# Reference.net
KiCad netlist of a schematic drawn in EAGLE
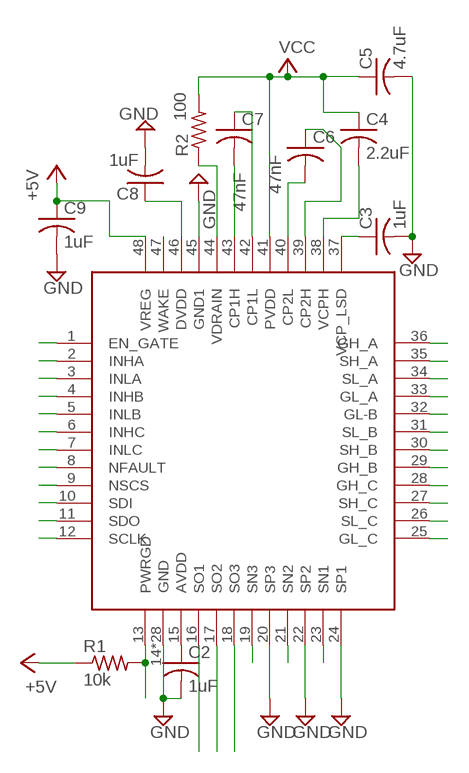
[diagram p0: schematic, sheet 1]

(export (version "E")
  (design (tool "Eeschema 10.0.6"))
  (components
    (comp (ref "C2")
      (value "1uF")
      (footprint "eagle-import:C0805")
      (libsource (lib "eagle-import") (part "C-USC0805"))
    )
    (comp (ref "C3")
      (value "1uF")
      (footprint "eagle-import:C0805")
      (libsource (lib "eagle-import") (part "C-USC0805"))
    )
    (comp (ref "C4")
      (value "2.2uF")
      (footprint "eagle-import:C0805")
      (libsource (lib "eagle-import") (part "C-USC0805"))
    )
    (comp (ref "C5")
      (value "4.7uF")
      (footprint "eagle-import:C0805")
      (libsource (lib "eagle-import") (part "C-USC0805"))
    )
    (comp (ref "C6")
      (value "47nF")
      (footprint "eagle-import:C0805")
      (libsource (lib "eagle-import") (part "C-USC0805"))
    )
    (comp (ref "C7")
      (value "47nF")
      (footprint "eagle-import:C0805")
      (libsource (lib "eagle-import") (part "C-USC0805"))
    )
    (comp (ref "C8")
      (value "1uF")
      (footprint "eagle-import:C0805")
      (libsource (lib "eagle-import") (part "C-USC0805"))
    )
    (comp (ref "C9")
      (value "1uF")
      (footprint "eagle-import:C0805")
      (libsource (lib "eagle-import") (part "C-USC0805"))
    )
    (comp (ref "R1")
      (value "10k")
      (footprint "eagle-import:M0805")
      (libsource (lib "eagle-import") (part "R-US_M0805"))
    )
    (comp (ref "R2")
      (value "100")
      (footprint "eagle-import:M0805")
      (libsource (lib "eagle-import") (part "R-US_M0805"))
    )
    (comp (ref "U$1")
      (value "DRV8305")
      (footprint "eagle-import:PFB_S-PQFP-G48")
      (libsource (lib "eagle-import") (part "DRV8305"))
    )
  )
  (nets
    (net (code "1") (name "+5V") (class "Default")
      (node (ref "C9") (pin "1") (pinfunction "1_1") (pintype "passive"))
      (node (ref "R1") (pin "1") (pinfunction "1_1") (pintype "passive"))
      (node (ref "U$1") (pin "48") (pinfunction "VREG_48") (pintype "bidirectional"))
    )
    (net (code "2") (name "/SL_A") (class "Default")
      (node (ref "U$1") (pin "23") (pinfunction "SN1_23") (pintype "bidirectional"))
      (node (ref "U$1") (pin "34") (pinfunction "SL_A_34") (pintype "bidirectional"))
    )
    (net (code "3") (name "/SL_B") (class "Default")
      (node (ref "U$1") (pin "21") (pinfunction "SN2_21") (pintype "bidirectional"))
      (node (ref "U$1") (pin "31") (pinfunction "SL_B_31") (pintype "bidirectional"))
    )
    (net (code "4") (name "/SL_C") (class "Default")
      (node (ref "U$1") (pin "19") (pinfunction "SN3_19") (pintype "bidirectional"))
      (node (ref "U$1") (pin "26") (pinfunction "SL_C_26") (pintype "bidirectional"))
    )
    (net (code "5") (name "GND") (class "Default")
      (node (ref "C2") (pin "2") (pinfunction "2_2") (pintype "passive"))
      (node (ref "C3") (pin "2") (pinfunction "2_2") (pintype "passive"))
      (node (ref "C5") (pin "2") (pinfunction "2_2") (pintype "passive"))
      (node (ref "C8") (pin "2") (pinfunction "2_2") (pintype "passive"))
      (node (ref "C9") (pin "2") (pinfunction "2_2") (pintype "passive"))
      (node (ref "U$1") (pin "14") (pinfunction "GND_14") (pintype "bidirectional"))
      (node (ref "U$1") (pin "20") (pinfunction "SP3_20") (pintype "bidirectional"))
      (node (ref "U$1") (pin "22") (pinfunction "SP2_22") (pintype "bidirectional"))
      (node (ref "U$1") (pin "24") (pinfunction "SP1_24") (pintype "bidirectional"))
      (node (ref "U$1") (pin "45") (pinfunction "GND1_45") (pintype "bidirectional"))
      (node (ref "U$1") (pin "P$1") (pinfunction "GND_P$1") (pintype "bidirectional"))
      (node (ref "U$1") (pin "P$10") (pinfunction "GND_P$10") (pintype "bidirectional"))
      (node (ref "U$1") (pin "P$11") (pinfunction "GND_P$11") (pintype "bidirectional"))
      (node (ref "U$1") (pin "P$12") (pinfunction "GND_P$12") (pintype "bidirectional"))
      (node (ref "U$1") (pin "P$13") (pinfunction "GND_P$13") (pintype "bidirectional"))
      (node (ref "U$1") (pin "P$14") (pinfunction "GND_P$14") (pintype "bidirectional"))
      (node (ref "U$1") (pin "P$15") (pinfunction "GND_P$15") (pintype "bidirectional"))
      (node (ref "U$1") (pin "P$16") (pinfunction "GND_P$16") (pintype "bidirectional"))
      (node (ref "U$1") (pin "P$17") (pinfunction "GND_P$17") (pintype "bidirectional"))
      (node (ref "U$1") (pin "P$18") (pinfunction "GND_P$18") (pintype "bidirectional"))
      (node (ref "U$1") (pin "P$19") (pinfunction "GND_P$19") (pintype "bidirectional"))
      (node (ref "U$1") (pin "P$2") (pinfunction "GND_P$2") (pintype "bidirectional"))
      (node (ref "U$1") (pin "P$20") (pinfunction "GND_P$20") (pintype "bidirectional"))
      (node (ref "U$1") (pin "P$21") (pinfunction "GND_P$21") (pintype "bidirectional"))
      (node (ref "U$1") (pin "P$22") (pinfunction "GND_P$22") (pintype "bidirectional"))
      (node (ref "U$1") (pin "P$23") (pinfunction "GND_P$23") (pintype "bidirectional"))
      (node (ref "U$1") (pin "P$24") (pinfunction "GND_P$24") (pintype "bidirectional"))
      (node (ref "U$1") (pin "P$25") (pinfunction "GND_P$25") (pintype "bidirectional"))
      (node (ref "U$1") (pin "P$26") (pinfunction "GND_P$26") (pintype "bidirectional"))
      (node (ref "U$1") (pin "P$27") (pinfunction "GND_P$27") (pintype "bidirectional"))
      (node (ref "U$1") (pin "P$3") (pinfunction "GND_P$3") (pintype "bidirectional"))
      (node (ref "U$1") (pin "P$4") (pinfunction "GND_P$4") (pintype "bidirectional"))
      (node (ref "U$1") (pin "P$5") (pinfunction "GND_P$5") (pintype "bidirectional"))
      (node (ref "U$1") (pin "P$6") (pinfunction "GND_P$6") (pintype "bidirectional"))
      (node (ref "U$1") (pin "P$7") (pinfunction "GND_P$7") (pintype "bidirectional"))
      (node (ref "U$1") (pin "P$8") (pinfunction "GND_P$8") (pintype "bidirectional"))
      (node (ref "U$1") (pin "P$9") (pinfunction "GND_P$9") (pintype "bidirectional"))
    )
    (net (code "6") (name "Net-(U$1-AVDD)") (class "Default")
      (node (ref "C2") (pin "1") (pinfunction "1_1") (pintype "passive"))
      (node (ref "U$1") (pin "15") (pinfunction "AVDD_15") (pintype "bidirectional"))
    )
    (net (code "7") (name "Net-(U$1-CP1H)") (class "Default")
      (node (ref "C7") (pin "2") (pinfunction "2_2") (pintype "passive"))
      (node (ref "U$1") (pin "43") (pinfunction "CP1H_43") (pintype "bidirectional"))
    )
    (net (code "8") (name "Net-(U$1-CP1L)") (class "Default")
      (node (ref "C7") (pin "1") (pinfunction "1_1") (pintype "passive"))
      (node (ref "U$1") (pin "42") (pinfunction "CP1L_42") (pintype "bidirectional"))
    )
    (net (code "9") (name "Net-(U$1-CP2H)") (class "Default")
      (node (ref "C6") (pin "1") (pinfunction "1_1") (pintype "passive"))
      (node (ref "U$1") (pin "39") (pinfunction "CP2H_39") (pintype "bidirectional"))
    )
    (net (code "10") (name "Net-(U$1-CP2L)") (class "Default")
      (node (ref "C6") (pin "2") (pinfunction "2_2") (pintype "passive"))
      (node (ref "U$1") (pin "40") (pinfunction "CP2L_40") (pintype "bidirectional"))
    )
    (net (code "11") (name "Net-(U$1-DVDD)") (class "Default")
      (node (ref "C8") (pin "1") (pinfunction "1_1") (pintype "passive"))
      (node (ref "U$1") (pin "46") (pinfunction "DVDD_46") (pintype "bidirectional"))
    )
    (net (code "12") (name "Net-(U$1-PWRGD)") (class "Default")
      (node (ref "R1") (pin "2") (pinfunction "2_2") (pintype "passive"))
      (node (ref "U$1") (pin "13") (pinfunction "PWRGD_13") (pintype "bidirectional"))
    )
    (net (code "13") (name "Net-(U$1-VCPH)") (class "Default")
      (node (ref "C4") (pin "2") (pinfunction "2_2") (pintype "passive"))
      (node (ref "U$1") (pin "38") (pinfunction "VCPH_38") (pintype "bidirectional"))
    )
    (net (code "14") (name "Net-(U$1-VCP_LSD)") (class "Default")
      (node (ref "C3") (pin "1") (pinfunction "1_1") (pintype "passive"))
      (node (ref "U$1") (pin "37") (pinfunction "VCP_LSD_37") (pintype "bidirectional"))
    )
    (net (code "15") (name "Net-(U$1-VDRAIN)") (class "Default")
      (node (ref "R2") (pin "1") (pinfunction "1_1") (pintype "passive"))
      (node (ref "U$1") (pin "44") (pinfunction "VDRAIN_44") (pintype "bidirectional"))
    )
    (net (code "16") (name "VCC") (class "Default")
      (node (ref "C4") (pin "1") (pinfunction "1_1") (pintype "passive"))
      (node (ref "C5") (pin "1") (pinfunction "1_1") (pintype "passive"))
      (node (ref "R2") (pin "2") (pinfunction "2_2") (pintype "passive"))
      (node (ref "U$1") (pin "41") (pinfunction "PVDD_41") (pintype "bidirectional"))
    )
    (net (code "17") (name "unconnected-(U$1-EN_GATE-Pad1)") (class "Default")
      (node (ref "U$1") (pin "1") (pinfunction "EN_GATE_1") (pintype "bidirectional"))
    )
    (net (code "18") (name "unconnected-(U$1-GH_A-Pad36)") (class "Default")
      (node (ref "U$1") (pin "36") (pinfunction "GH_A_36") (pintype "bidirectional"))
    )
    (net (code "19") (name "unconnected-(U$1-GH_B-Pad29)") (class "Default")
      (node (ref "U$1") (pin "29") (pinfunction "GH_B_29") (pintype "bidirectional"))
    )
    (net (code "20") (name "unconnected-(U$1-GH_C-Pad28)") (class "Default")
      (node (ref "U$1") (pin "28") (pinfunction "GH_C_28") (pintype "bidirectional"))
    )
    (net (code "21") (name "unconnected-(U$1-GL-B-Pad32)") (class "Default")
      (node (ref "U$1") (pin "32") (pinfunction "GL-B_32") (pintype "bidirectional"))
    )
    (net (code "22") (name "unconnected-(U$1-GL_A-Pad33)") (class "Default")
      (node (ref "U$1") (pin "33") (pinfunction "GL_A_33") (pintype "bidirectional"))
    )
    (net (code "23") (name "unconnected-(U$1-GL_C-Pad25)") (class "Default")
      (node (ref "U$1") (pin "25") (pinfunction "GL_C_25") (pintype "bidirectional"))
    )
    (net (code "24") (name "unconnected-(U$1-INHA-Pad2)") (class "Default")
      (node (ref "U$1") (pin "2") (pinfunction "INHA_2") (pintype "bidirectional"))
    )
    (net (code "25") (name "unconnected-(U$1-INHB-Pad4)") (class "Default")
      (node (ref "U$1") (pin "4") (pinfunction "INHB_4") (pintype "bidirectional"))
    )
    (net (code "26") (name "unconnected-(U$1-INHC-Pad6)") (class "Default")
      (node (ref "U$1") (pin "6") (pinfunction "INHC_6") (pintype "bidirectional"))
    )
    (net (code "27") (name "unconnected-(U$1-INLA-Pad3)") (class "Default")
      (node (ref "U$1") (pin "3") (pinfunction "INLA_3") (pintype "bidirectional"))
    )
    (net (code "28") (name "unconnected-(U$1-INLB-Pad5)") (class "Default")
      (node (ref "U$1") (pin "5") (pinfunction "INLB_5") (pintype "bidirectional"))
    )
    (net (code "29") (name "unconnected-(U$1-INLC-Pad7)") (class "Default")
      (node (ref "U$1") (pin "7") (pinfunction "INLC_7") (pintype "bidirectional"))
    )
    (net (code "30") (name "unconnected-(U$1-NFAULT-Pad8)") (class "Default")
      (node (ref "U$1") (pin "8") (pinfunction "NFAULT_8") (pintype "bidirectional"))
    )
    (net (code "31") (name "unconnected-(U$1-NSCS-Pad9)") (class "Default")
      (node (ref "U$1") (pin "9") (pinfunction "NSCS_9") (pintype "bidirectional"))
    )
    (net (code "32") (name "unconnected-(U$1-SCLK-Pad12)") (class "Default")
      (node (ref "U$1") (pin "12") (pinfunction "SCLK_12") (pintype "bidirectional"))
    )
    (net (code "33") (name "unconnected-(U$1-SDI-Pad10)") (class "Default")
      (node (ref "U$1") (pin "10") (pinfunction "SDI_10") (pintype "bidirectional"))
    )
    (net (code "34") (name "unconnected-(U$1-SDO-Pad11)") (class "Default")
      (node (ref "U$1") (pin "11") (pinfunction "SDO_11") (pintype "bidirectional"))
    )
    (net (code "35") (name "unconnected-(U$1-SH_A-Pad35)") (class "Default")
      (node (ref "U$1") (pin "35") (pinfunction "SH_A_35") (pintype "bidirectional"))
    )
    (net (code "36") (name "unconnected-(U$1-SH_B-Pad30)") (class "Default")
      (node (ref "U$1") (pin "30") (pinfunction "SH_B_30") (pintype "bidirectional"))
    )
    (net (code "37") (name "unconnected-(U$1-SH_C-Pad27)") (class "Default")
      (node (ref "U$1") (pin "27") (pinfunction "SH_C_27") (pintype "bidirectional"))
    )
    (net (code "38") (name "unconnected-(U$1-SO1-Pad16)") (class "Default")
      (node (ref "U$1") (pin "16") (pinfunction "SO1_16") (pintype "bidirectional"))
    )
    (net (code "39") (name "unconnected-(U$1-SO2-Pad17)") (class "Default")
      (node (ref "U$1") (pin "17") (pinfunction "SO2_17") (pintype "bidirectional"))
    )
    (net (code "40") (name "unconnected-(U$1-SO3-Pad18)") (class "Default")
      (node (ref "U$1") (pin "18") (pinfunction "SO3_18") (pintype "bidirectional"))
    )
    (net (code "41") (name "unconnected-(U$1-WAKE-Pad47)") (class "Default")
      (node (ref "U$1") (pin "47") (pinfunction "WAKE_47") (pintype "bidirectional"))
    )
  )
)
